# sub_module.net
KiCad netlist of a schematic drawn in EAGLE
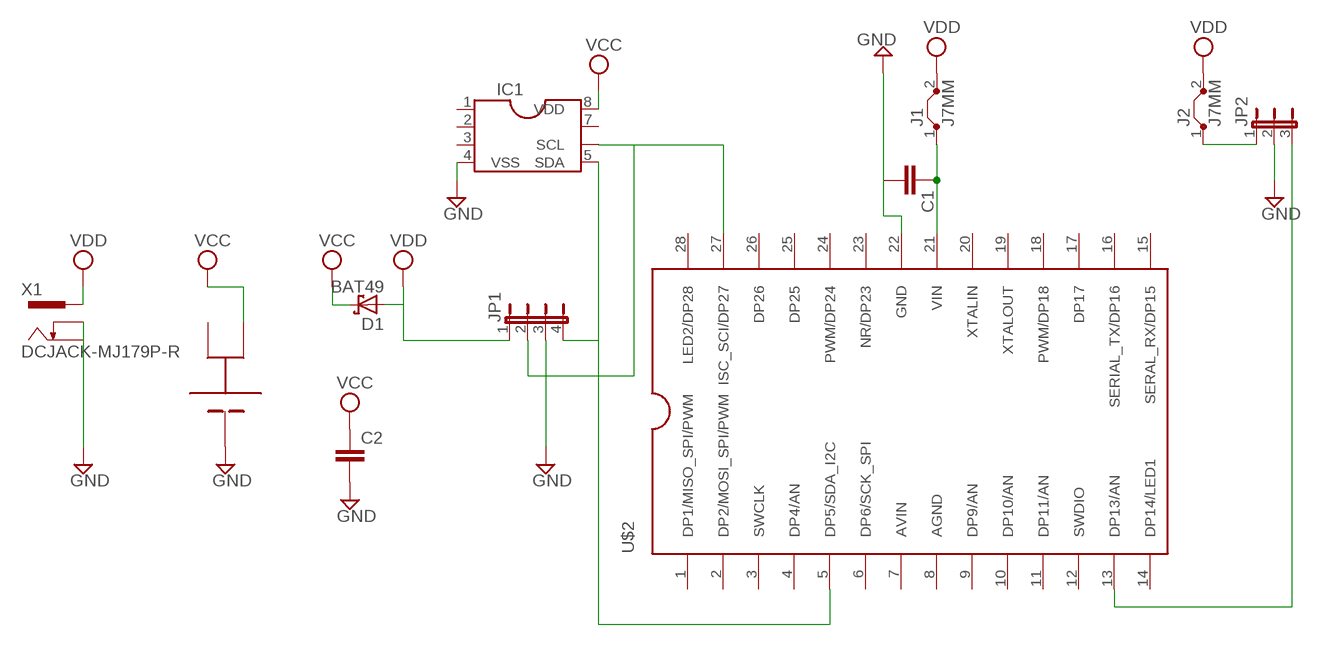
[diagram p0: schematic, sheet 1]

(export (version "E")
  (design (tool "Eeschema 10.0.6"))
  (components
    (comp (ref "C1")
      (value "C-EUC2012")
      (footprint "eagle-import:C2012")
      (libsource (lib "eagle-import") (part "C-EUC2012"))
    )
    (comp (ref "C2")
      (value "C-EUC2012")
      (footprint "eagle-import:C2012")
      (libsource (lib "eagle-import") (part "C-EUC2012"))
    )
    (comp (ref "D1")
      (value "BAT49")
      (footprint "eagle-import:DO41-10")
      (libsource (lib "eagle-import") (part "BAT49"))
    )
    (comp (ref "IC1")
      (value "DIL8S")
      (footprint "eagle-import:SOCKET-08")
      (libsource (lib "eagle-import") (part "DIL8S"))
    )
    (comp (ref "J1")
      (value "J7MM")
      (footprint "eagle-import:07")
      (libsource (lib "eagle-import") (part "J7MM"))
    )
    (comp (ref "J2")
      (value "J7MM")
      (footprint "eagle-import:07")
      (libsource (lib "eagle-import") (part "J7MM"))
    )
    (comp (ref "JP1")
      (value "JP4E")
      (footprint "eagle-import:JP4")
      (libsource (lib "eagle-import") (part "JP4E"))
    )
    (comp (ref "JP2")
      (value "JP2E")
      (footprint "eagle-import:JP2")
      (libsource (lib "eagle-import") (part "JP2E"))
    )
    (comp (ref "U$1")
      (value "CR2032-HOLDER")
      (footprint "eagle-import:CR2032-HOLDER")
      (libsource (lib "eagle-import") (part "CR2032-HOLDER"))
    )
    (comp (ref "U$2")
      (value "LPC1114FDH28")
      (footprint "eagle-import:TSSOP28")
      (libsource (lib "eagle-import") (part "LPC1114FDH28"))
    )
    (comp (ref "X1")
      (value "DCJACK-MJ179P-R")
      (footprint "eagle-import:MJ-179P-R")
      (libsource (lib "eagle-import") (part "DCJACK-MJ179P-R"))
    )
  )
  (nets
    (net (code "1") (name "/3VL") (class "Default")
      (node (ref "U$1") (pin "3VL") (pinfunction "3VL_3VL") (pintype "power_in"))
    )
    (net (code "2") (name "/AGND") (class "Default")
      (node (ref "U$2") (pin "8") (pinfunction "AGND_8") (pintype "power_in"))
    )
    (net (code "3") (name "/AVIN") (class "Default")
      (node (ref "U$2") (pin "7") (pinfunction "AVIN_7") (pintype "power_in"))
    )
    (net (code "4") (name "GND") (class "Default")
      (node (ref "C1") (pin "2") (pinfunction "2_2") (pintype "passive"))
      (node (ref "C2") (pin "2") (pinfunction "2_2") (pintype "passive"))
      (node (ref "IC1") (pin "4") (pinfunction "VSS_4") (pintype "passive"))
      (node (ref "JP1") (pin "3") (pinfunction "3_3") (pintype "passive"))
      (node (ref "JP2") (pin "2") (pinfunction "2_2") (pintype "passive"))
      (node (ref "U$1") (pin "GND") (pinfunction "GND_GND") (pintype "power_in"))
      (node (ref "U$2") (pin "22") (pinfunction "GND_22") (pintype "power_in"))
      (node (ref "X1") (pin "2") (pinfunction "2_2") (pintype "passive"))
      (node (ref "X1") (pin "3") (pinfunction "3_3") (pintype "passive"))
    )
    (net (code "5") (name "Net-(IC1-SCL)") (class "Default")
      (node (ref "IC1") (pin "6") (pinfunction "SCL_6") (pintype "passive"))
      (node (ref "JP1") (pin "2") (pinfunction "2_2") (pintype "passive"))
      (node (ref "U$2") (pin "27") (pinfunction "ISC_SCI/DP27_27") (pintype "bidirectional"))
    )
    (net (code "6") (name "Net-(IC1-SDA)") (class "Default")
      (node (ref "IC1") (pin "5") (pinfunction "SDA_5") (pintype "passive"))
      (node (ref "JP1") (pin "4") (pinfunction "4_4") (pintype "passive"))
      (node (ref "U$2") (pin "5") (pinfunction "DP5/SDA_I2C_5") (pintype "bidirectional"))
    )
    (net (code "7") (name "Net-(J2-Pad1)") (class "Default")
      (node (ref "J2") (pin "1") (pinfunction "1_1") (pintype "passive"))
      (node (ref "JP2") (pin "1") (pinfunction "1_1") (pintype "passive"))
    )
    (net (code "8") (name "Net-(U$2-DP13{slash}AN)") (class "Default")
      (node (ref "JP2") (pin "3") (pinfunction "3_3") (pintype "passive"))
      (node (ref "U$2") (pin "13") (pinfunction "DP13/AN_13") (pintype "bidirectional"))
    )
    (net (code "9") (name "Net-(U$2-VIN)") (class "Default")
      (node (ref "C1") (pin "1") (pinfunction "1_1") (pintype "passive"))
      (node (ref "J1") (pin "1") (pinfunction "1_1") (pintype "passive"))
      (node (ref "U$2") (pin "21") (pinfunction "VIN_21") (pintype "power_in"))
    )
    (net (code "10") (name "VCC") (class "Default")
      (node (ref "C2") (pin "1") (pinfunction "1_1") (pintype "passive"))
      (node (ref "D1") (pin "C") (pinfunction "C_C") (pintype "passive"))
      (node (ref "IC1") (pin "8") (pinfunction "VDD_8") (pintype "passive"))
      (node (ref "U$1") (pin "3VR") (pinfunction "3VR_3VR") (pintype "power_in"))
    )
    (net (code "11") (name "VDD") (class "Default")
      (node (ref "D1") (pin "A") (pinfunction "A_A") (pintype "passive"))
      (node (ref "J1") (pin "2") (pinfunction "2_2") (pintype "passive"))
      (node (ref "J2") (pin "2") (pinfunction "2_2") (pintype "passive"))
      (node (ref "JP1") (pin "1") (pinfunction "1_1") (pintype "passive"))
      (node (ref "X1") (pin "1") (pinfunction "1_1") (pintype "passive"))
    )
    (net (code "12") (name "unconnected-(IC1-CLKOE-Pad1)") (class "Default")
      (node (ref "IC1") (pin "1") (pinfunction "CLKOE_1") (pintype "passive"))
    )
    (net (code "13") (name "unconnected-(IC1-CLKOUT-Pad2)") (class "Default")
      (node (ref "IC1") (pin "2") (pinfunction "CLKOUT_2") (pintype "passive"))
    )
    (net (code "14") (name "unconnected-(IC1-INT-Pad3)") (class "Default")
      (node (ref "IC1") (pin "3") (pinfunction "INT_3") (pintype "passive"))
    )
    (net (code "15") (name "unconnected-(IC1-V.C.-Pad7)") (class "Default")
      (node (ref "IC1") (pin "7") (pinfunction "V.C._7") (pintype "passive"))
    )
    (net (code "16") (name "unconnected-(U$2-DP1{slash}MISO_SPI{slash}PWM-Pad1)") (class "Default")
      (node (ref "U$2") (pin "1") (pinfunction "DP1/MISO_SPI/PWM_1") (pintype "bidirectional"))
    )
    (net (code "17") (name "unconnected-(U$2-DP2{slash}MOSI_SPI{slash}PWM-Pad2)") (class "Default")
      (node (ref "U$2") (pin "2") (pinfunction "DP2/MOSI_SPI/PWM_2") (pintype "bidirectional"))
    )
    (net (code "18") (name "unconnected-(U$2-DP4{slash}AN-Pad4)") (class "Default")
      (node (ref "U$2") (pin "4") (pinfunction "DP4/AN_4") (pintype "bidirectional"))
    )
    (net (code "19") (name "unconnected-(U$2-DP6{slash}SCK_SPI-Pad6)") (class "Default")
      (node (ref "U$2") (pin "6") (pinfunction "DP6/SCK_SPI_6") (pintype "bidirectional"))
    )
    (net (code "20") (name "unconnected-(U$2-DP9{slash}AN-Pad9)") (class "Default")
      (node (ref "U$2") (pin "9") (pinfunction "DP9/AN_9") (pintype "bidirectional"))
    )
    (net (code "21") (name "unconnected-(U$2-DP10{slash}AN-Pad10)") (class "Default")
      (node (ref "U$2") (pin "10") (pinfunction "DP10/AN_10") (pintype "bidirectional"))
    )
    (net (code "22") (name "unconnected-(U$2-DP11{slash}AN-Pad11)") (class "Default")
      (node (ref "U$2") (pin "11") (pinfunction "DP11/AN_11") (pintype "bidirectional"))
    )
    (net (code "23") (name "unconnected-(U$2-DP14{slash}LED1-Pad14)") (class "Default")
      (node (ref "U$2") (pin "14") (pinfunction "DP14/LED1_14") (pintype "bidirectional"))
    )
    (net (code "24") (name "unconnected-(U$2-DP17-Pad17)") (class "Default")
      (node (ref "U$2") (pin "17") (pinfunction "DP17_17") (pintype "bidirectional"))
    )
    (net (code "25") (name "unconnected-(U$2-DP25-Pad25)") (class "Default")
      (node (ref "U$2") (pin "25") (pinfunction "DP25_25") (pintype "bidirectional"))
    )
    (net (code "26") (name "unconnected-(U$2-DP26-Pad26)") (class "Default")
      (node (ref "U$2") (pin "26") (pinfunction "DP26_26") (pintype "bidirectional"))
    )
    (net (code "27") (name "unconnected-(U$2-LED2{slash}DP28-Pad28)") (class "Default")
      (node (ref "U$2") (pin "28") (pinfunction "LED2/DP28_28") (pintype "bidirectional"))
    )
    (net (code "28") (name "unconnected-(U$2-NR{slash}DP23-Pad23)") (class "Default")
      (node (ref "U$2") (pin "23") (pinfunction "NR/DP23_23") (pintype "bidirectional"))
    )
    (net (code "29") (name "unconnected-(U$2-PWM{slash}DP18-Pad18)") (class "Default")
      (node (ref "U$2") (pin "18") (pinfunction "PWM/DP18_18") (pintype "bidirectional"))
    )
    (net (code "30") (name "unconnected-(U$2-PWM{slash}DP24-Pad24)") (class "Default")
      (node (ref "U$2") (pin "24") (pinfunction "PWM/DP24_24") (pintype "bidirectional"))
    )
    (net (code "31") (name "unconnected-(U$2-SERAL_RX{slash}DP15-Pad15)") (class "Default")
      (node (ref "U$2") (pin "15") (pinfunction "SERAL_RX/DP15_15") (pintype "bidirectional"))
    )
    (net (code "32") (name "unconnected-(U$2-SERIAL_TX{slash}DP16-Pad16)") (class "Default")
      (node (ref "U$2") (pin "16") (pinfunction "SERIAL_TX/DP16_16") (pintype "bidirectional"))
    )
    (net (code "33") (name "unconnected-(U$2-SWCLK-Pad3)") (class "Default")
      (node (ref "U$2") (pin "3") (pinfunction "SWCLK_3") (pintype "bidirectional"))
    )
    (net (code "34") (name "unconnected-(U$2-SWDIO-Pad12)") (class "Default")
      (node (ref "U$2") (pin "12") (pinfunction "SWDIO_12") (pintype "bidirectional"))
    )
    (net (code "35") (name "unconnected-(U$2-XTALIN-Pad20)") (class "Default")
      (node (ref "U$2") (pin "20") (pinfunction "XTALIN_20") (pintype "input"))
    )
    (net (code "36") (name "unconnected-(U$2-XTALOUT-Pad19)") (class "Default")
      (node (ref "U$2") (pin "19") (pinfunction "XTALOUT_19") (pintype "output"))
    )
  )
)
